# Folie_KeyBoard_V100_MAIN.net
KiCad netlist of a schematic drawn in Altium Designer
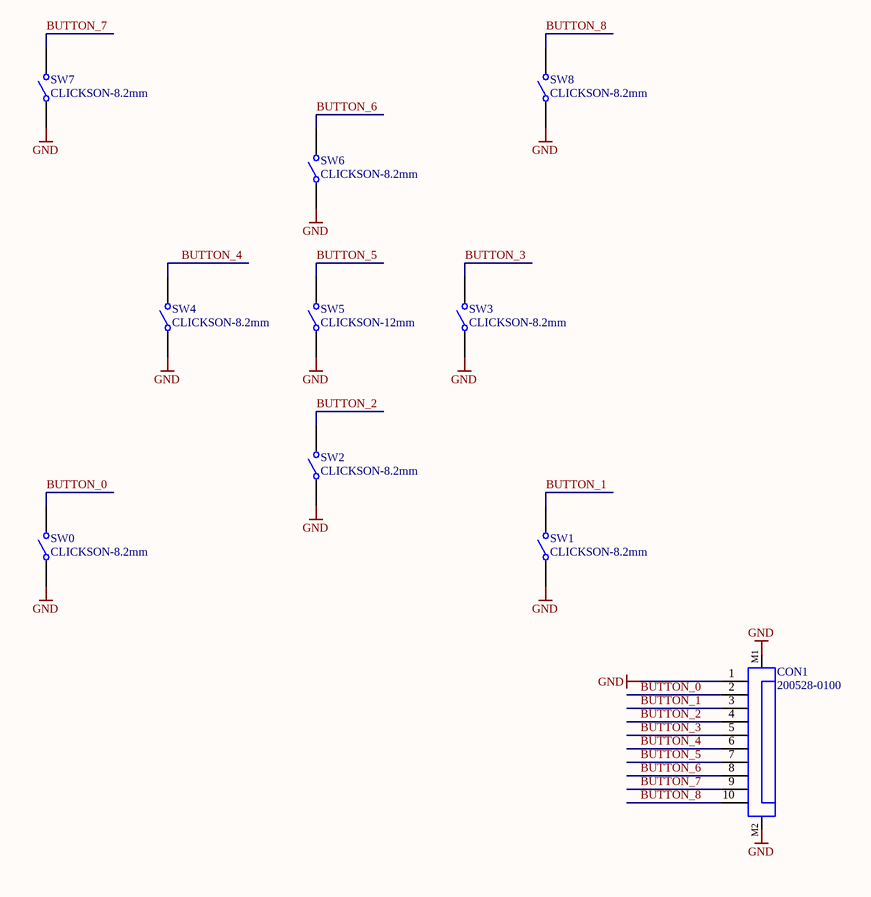
[diagram p0: Folie_KeyBoard_V100_MAIN.SchDoc]

(export (version "E")
  (design (tool "Eeschema 10.0.6"))
  (components
    (comp (ref "CON1")
      (value "200528-0100")
      (footprint "CON_FPC10_1MM_MOLEX_200528-0100")
      (description "FFC / FPC Board Connector, 1 mm, 10 Contacts, Receptacle, Easy-On, Surface Mount")
      (fields (field (name "PART NUMBER") "CON_FPC_MOLEX_200528-0100"))
      (libsource (lib "ALTIUM_DB_LIB") (part "FPC_10PIN"))
    )
    (comp (ref "SW0")
      (value "CLICKSON-8.2mm")
      (footprint "CLICKSON-8.2mm")
      (description "CLICKSON-8.2mm for folie tastature")
      (libsource (lib "ALTIUM_DB_LIB") (part "SWITCH_SPST"))
    )
    (comp (ref "SW1")
      (value "CLICKSON-8.2mm")
      (footprint "CLICKSON-8.2mm")
      (description "CLICKSON-8.2mm for folie tastature")
      (libsource (lib "ALTIUM_DB_LIB") (part "SWITCH_SPST"))
    )
    (comp (ref "SW2")
      (value "CLICKSON-8.2mm")
      (footprint "CLICKSON-8.2mm")
      (description "CLICKSON-8.2mm for folie tastature")
      (libsource (lib "ALTIUM_DB_LIB") (part "SWITCH_SPST"))
    )
    (comp (ref "SW3")
      (value "CLICKSON-8.2mm")
      (footprint "CLICKSON-8.2mm")
      (description "CLICKSON-8.2mm for folie tastature")
      (libsource (lib "ALTIUM_DB_LIB") (part "SWITCH_SPST"))
    )
    (comp (ref "SW4")
      (value "CLICKSON-8.2mm")
      (footprint "CLICKSON-8.2mm")
      (description "CLICKSON-8.2mm for folie tastature")
      (libsource (lib "ALTIUM_DB_LIB") (part "SWITCH_SPST"))
    )
    (comp (ref "SW5")
      (value "CLICKSON-12mm")
      (footprint "CLICKSON-12mm")
      (description "CLICKSON-12mm for folie tastature")
      (libsource (lib "ALTIUM_DB_LIB") (part "SWITCH_SPST"))
    )
    (comp (ref "SW6")
      (value "CLICKSON-8.2mm")
      (footprint "CLICKSON-8.2mm")
      (description "CLICKSON-8.2mm for folie tastature")
      (libsource (lib "ALTIUM_DB_LIB") (part "SWITCH_SPST"))
    )
    (comp (ref "SW7")
      (value "CLICKSON-8.2mm")
      (footprint "CLICKSON-8.2mm")
      (description "CLICKSON-8.2mm for folie tastature")
      (libsource (lib "ALTIUM_DB_LIB") (part "SWITCH_SPST"))
    )
    (comp (ref "SW8")
      (value "CLICKSON-8.2mm")
      (footprint "CLICKSON-8.2mm")
      (description "CLICKSON-8.2mm for folie tastature")
      (libsource (lib "ALTIUM_DB_LIB") (part "SWITCH_SPST"))
    )
  )
  (nets
    (net (code "1") (name "/BUTTON_0") (class "Default")
      (node (ref "CON1") (pin "2") (pinfunction "2_2") (pintype "passive"))
      (node (ref "SW0") (pin "2") (pinfunction "2_2") (pintype "passive"))
    )
    (net (code "2") (name "/BUTTON_1") (class "Default")
      (node (ref "CON1") (pin "3") (pinfunction "3_3") (pintype "passive"))
      (node (ref "SW1") (pin "2") (pinfunction "2_2") (pintype "passive"))
    )
    (net (code "3") (name "/BUTTON_2") (class "Default")
      (node (ref "CON1") (pin "4") (pinfunction "4_4") (pintype "passive"))
      (node (ref "SW2") (pin "2") (pinfunction "2_2") (pintype "passive"))
    )
    (net (code "4") (name "/BUTTON_3") (class "Default")
      (node (ref "CON1") (pin "5") (pinfunction "5_5") (pintype "passive"))
      (node (ref "SW3") (pin "2") (pinfunction "2_2") (pintype "passive"))
    )
    (net (code "5") (name "/BUTTON_4") (class "Default")
      (node (ref "CON1") (pin "6") (pinfunction "6_6") (pintype "passive"))
      (node (ref "SW4") (pin "2") (pinfunction "2_2") (pintype "passive"))
    )
    (net (code "6") (name "/BUTTON_5") (class "Default")
      (node (ref "CON1") (pin "7") (pinfunction "7_7") (pintype "passive"))
      (node (ref "SW5") (pin "2") (pinfunction "2_2") (pintype "passive"))
    )
    (net (code "7") (name "/BUTTON_6") (class "Default")
      (node (ref "CON1") (pin "8") (pinfunction "8_8") (pintype "passive"))
      (node (ref "SW6") (pin "2") (pinfunction "2_2") (pintype "passive"))
    )
    (net (code "8") (name "/BUTTON_7") (class "Default")
      (node (ref "CON1") (pin "9") (pinfunction "9_9") (pintype "passive"))
      (node (ref "SW7") (pin "2") (pinfunction "2_2") (pintype "passive"))
    )
    (net (code "9") (name "/BUTTON_8") (class "Default")
      (node (ref "CON1") (pin "10") (pinfunction "10_10") (pintype "passive"))
      (node (ref "SW8") (pin "2") (pinfunction "2_2") (pintype "passive"))
    )
    (net (code "10") (name "GND") (class "Default")
      (node (ref "CON1") (pin "1") (pinfunction "1_1") (pintype "passive"))
      (node (ref "CON1") (pin "M1") (pinfunction "M1_M1") (pintype "passive"))
      (node (ref "CON1") (pin "M2") (pinfunction "M2_M2") (pintype "passive"))
      (node (ref "SW0") (pin "1") (pinfunction "1_1") (pintype "passive"))
      (node (ref "SW1") (pin "1") (pinfunction "1_1") (pintype "passive"))
      (node (ref "SW2") (pin "1") (pinfunction "1_1") (pintype "passive"))
      (node (ref "SW3") (pin "1") (pinfunction "1_1") (pintype "passive"))
      (node (ref "SW4") (pin "1") (pinfunction "1_1") (pintype "passive"))
      (node (ref "SW5") (pin "1") (pinfunction "1_1") (pintype "passive"))
      (node (ref "SW6") (pin "1") (pinfunction "1_1") (pintype "passive"))
      (node (ref "SW7") (pin "1") (pinfunction "1_1") (pintype "passive"))
      (node (ref "SW8") (pin "1") (pinfunction "1_1") (pintype "passive"))
    )
  )
)
